# esp8266Remote.net
KiCad netlist of a schematic drawn in EAGLE
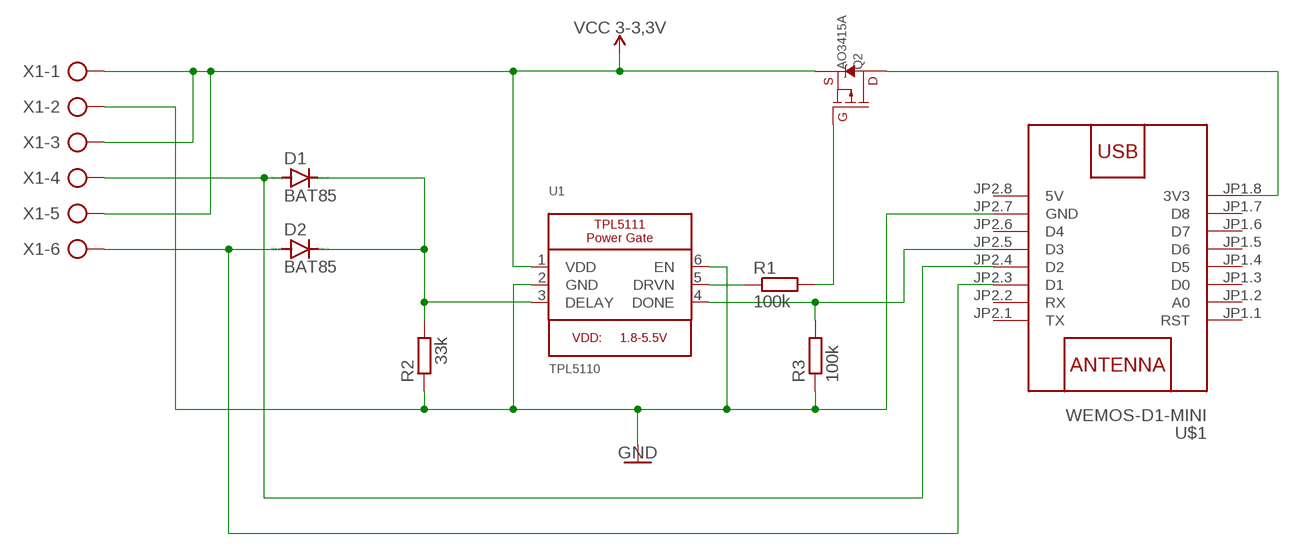
[diagram p0: schematic, sheet 1]

(export (version "E")
  (design (tool "Eeschema 10.0.6"))
  (components
    (comp (ref "D1")
      (value "BAT85")
      (footprint "eagle-import:D-5")
      (libsource (lib "eagle-import") (part "DIODE-D-5"))
    )
    (comp (ref "D2")
      (value "BAT85")
      (footprint "eagle-import:D-5")
      (libsource (lib "eagle-import") (part "DIODE-D-5"))
    )
    (comp (ref "Q2")
      (value "AO3415A")
      (footprint "eagle-import:HDRV3W64P254_1X3_1016X400X838B")
      (libsource (lib "eagle-import") (part "MOSFET_PCHDIL3-SOT23-3-ADPATER"))
    )
    (comp (ref "R1")
      (value "100k")
      (footprint "eagle-import:0207_12")
      (libsource (lib "eagle-import") (part "R-EU_0207/12"))
    )
    (comp (ref "R2")
      (value "33k")
      (footprint "eagle-import:0204_5")
      (libsource (lib "eagle-import") (part "R-EU_0204/5"))
    )
    (comp (ref "R3")
      (value "100k")
      (footprint "eagle-import:0204_5")
      (libsource (lib "eagle-import") (part "R-EU_0204/5"))
    )
    (comp (ref "U$1")
      (value "WEMOS-D1-MINI")
      (footprint "eagle-import:WEMOS-D1-MINI")
      (libsource (lib "eagle-import") (part "WEMOS-D1-MINI"))
    )
    (comp (ref "U1")
      (value "TPL5110")
      (footprint "eagle-import:DIP762W53P254L866H300Q6B")
      (libsource (lib "eagle-import") (part "TPL5111DIL-6-ADAPTER"))
    )
    (comp (ref "X1")
      (value "AK500/6")
      (footprint "eagle-import:AK500_6")
      (libsource (lib "eagle-import") (part "AK500/6"))
    )
  )
  (nets
    (net (code "1") (name "/5V") (class "Default")
      (node (ref "U$1") (pin "JP2.8") (pinfunction "5V_JP2.8") (pintype "power_in"))
    )
    (net (code "2") (name "GND") (class "Default")
      (node (ref "R2") (pin "1") (pinfunction "1_1") (pintype "passive"))
      (node (ref "R3") (pin "1") (pinfunction "1_1") (pintype "passive"))
      (node (ref "U$1") (pin "JP2.7") (pinfunction "GND_JP2.7") (pintype "power_in"))
      (node (ref "U1") (pin "2") (pinfunction "GND_2") (pintype "power_in"))
      (node (ref "U1") (pin "6") (pinfunction "EN_6") (pintype "input"))
      (node (ref "X1") (pin "2") (pinfunction "KL_2") (pintype "passive"))
    )
    (net (code "3") (name "Net-(Q2-D)") (class "Default")
      (node (ref "Q2") (pin "2") (pinfunction "D_2") (pintype "bidirectional"))
      (node (ref "U$1") (pin "JP1.8") (pinfunction "3V3_JP1.8") (pintype "power_in"))
    )
    (net (code "4") (name "Net-(Q2-G)") (class "Default")
      (node (ref "Q2") (pin "3") (pinfunction "G_3") (pintype "bidirectional"))
      (node (ref "R1") (pin "2") (pinfunction "2_2") (pintype "passive"))
    )
    (net (code "5") (name "Net-(U$1-D1)") (class "Default")
      (node (ref "D2") (pin "A") (pinfunction "A_A") (pintype "passive"))
      (node (ref "U$1") (pin "JP2.3") (pinfunction "D1_JP2.3") (pintype "bidirectional"))
      (node (ref "X1") (pin "6") (pinfunction "KL_6") (pintype "passive"))
    )
    (net (code "6") (name "Net-(U$1-D2)") (class "Default")
      (node (ref "D1") (pin "A") (pinfunction "A_A") (pintype "passive"))
      (node (ref "U$1") (pin "JP2.4") (pinfunction "D2_JP2.4") (pintype "bidirectional"))
      (node (ref "X1") (pin "4") (pinfunction "KL_4") (pintype "passive"))
    )
    (net (code "7") (name "Net-(U$1-D3)") (class "Default")
      (node (ref "R3") (pin "2") (pinfunction "2_2") (pintype "passive"))
      (node (ref "U$1") (pin "JP2.5") (pinfunction "D3_JP2.5") (pintype "bidirectional"))
      (node (ref "U1") (pin "4") (pinfunction "DONE_4") (pintype "input"))
    )
    (net (code "8") (name "Net-(U1-DELAY)") (class "Default")
      (node (ref "D1") (pin "C") (pinfunction "C_C") (pintype "passive"))
      (node (ref "D2") (pin "C") (pinfunction "C_C") (pintype "passive"))
      (node (ref "R2") (pin "2") (pinfunction "2_2") (pintype "passive"))
      (node (ref "U1") (pin "3") (pinfunction "DELAY_3") (pintype "input"))
    )
    (net (code "9") (name "Net-(U1-DRVN)") (class "Default")
      (node (ref "R1") (pin "1") (pinfunction "1_1") (pintype "passive"))
      (node (ref "U1") (pin "5") (pinfunction "DRVN_5") (pintype "output"))
    )
    (net (code "10") (name "VCC 3-3,3V") (class "Default")
      (node (ref "Q2") (pin "1") (pinfunction "S_1") (pintype "bidirectional"))
      (node (ref "U1") (pin "1") (pinfunction "VDD_1") (pintype "power_in"))
      (node (ref "X1") (pin "1") (pinfunction "KL_1") (pintype "passive"))
      (node (ref "X1") (pin "3") (pinfunction "KL_3") (pintype "passive"))
      (node (ref "X1") (pin "5") (pinfunction "KL_5") (pintype "passive"))
    )
    (net (code "11") (name "unconnected-(U$1-A0-PadJP1.2)") (class "Default")
      (node (ref "U$1") (pin "JP1.2") (pinfunction "A0_JP1.2") (pintype "bidirectional"))
    )
    (net (code "12") (name "unconnected-(U$1-D0-PadJP1.3)") (class "Default")
      (node (ref "U$1") (pin "JP1.3") (pinfunction "D0_JP1.3") (pintype "bidirectional"))
    )
    (net (code "13") (name "unconnected-(U$1-D4-PadJP2.6)") (class "Default")
      (node (ref "U$1") (pin "JP2.6") (pinfunction "D4_JP2.6") (pintype "bidirectional"))
    )
    (net (code "14") (name "unconnected-(U$1-D5-PadJP1.4)") (class "Default")
      (node (ref "U$1") (pin "JP1.4") (pinfunction "D5_JP1.4") (pintype "bidirectional"))
    )
    (net (code "15") (name "unconnected-(U$1-D6-PadJP1.5)") (class "Default")
      (node (ref "U$1") (pin "JP1.5") (pinfunction "D6_JP1.5") (pintype "bidirectional"))
    )
    (net (code "16") (name "unconnected-(U$1-D7-PadJP1.6)") (class "Default")
      (node (ref "U$1") (pin "JP1.6") (pinfunction "D7_JP1.6") (pintype "bidirectional"))
    )
    (net (code "17") (name "unconnected-(U$1-D8-PadJP1.7)") (class "Default")
      (node (ref "U$1") (pin "JP1.7") (pinfunction "D8_JP1.7") (pintype "bidirectional"))
    )
    (net (code "18") (name "unconnected-(U$1-RST-PadJP1.1)") (class "Default")
      (node (ref "U$1") (pin "JP1.1") (pinfunction "RST_JP1.1") (pintype "bidirectional"))
    )
    (net (code "19") (name "unconnected-(U$1-RX-PadJP2.2)") (class "Default")
      (node (ref "U$1") (pin "JP2.2") (pinfunction "RX_JP2.2") (pintype "bidirectional"))
    )
    (net (code "20") (name "unconnected-(U$1-TX-PadJP2.1)") (class "Default")
      (node (ref "U$1") (pin "JP2.1") (pinfunction "TX_JP2.1") (pintype "bidirectional"))
    )
  )
)
